# LoRa_ST_Sensor_Node_v1_0.net
KiCad netlist of a schematic drawn in EAGLE
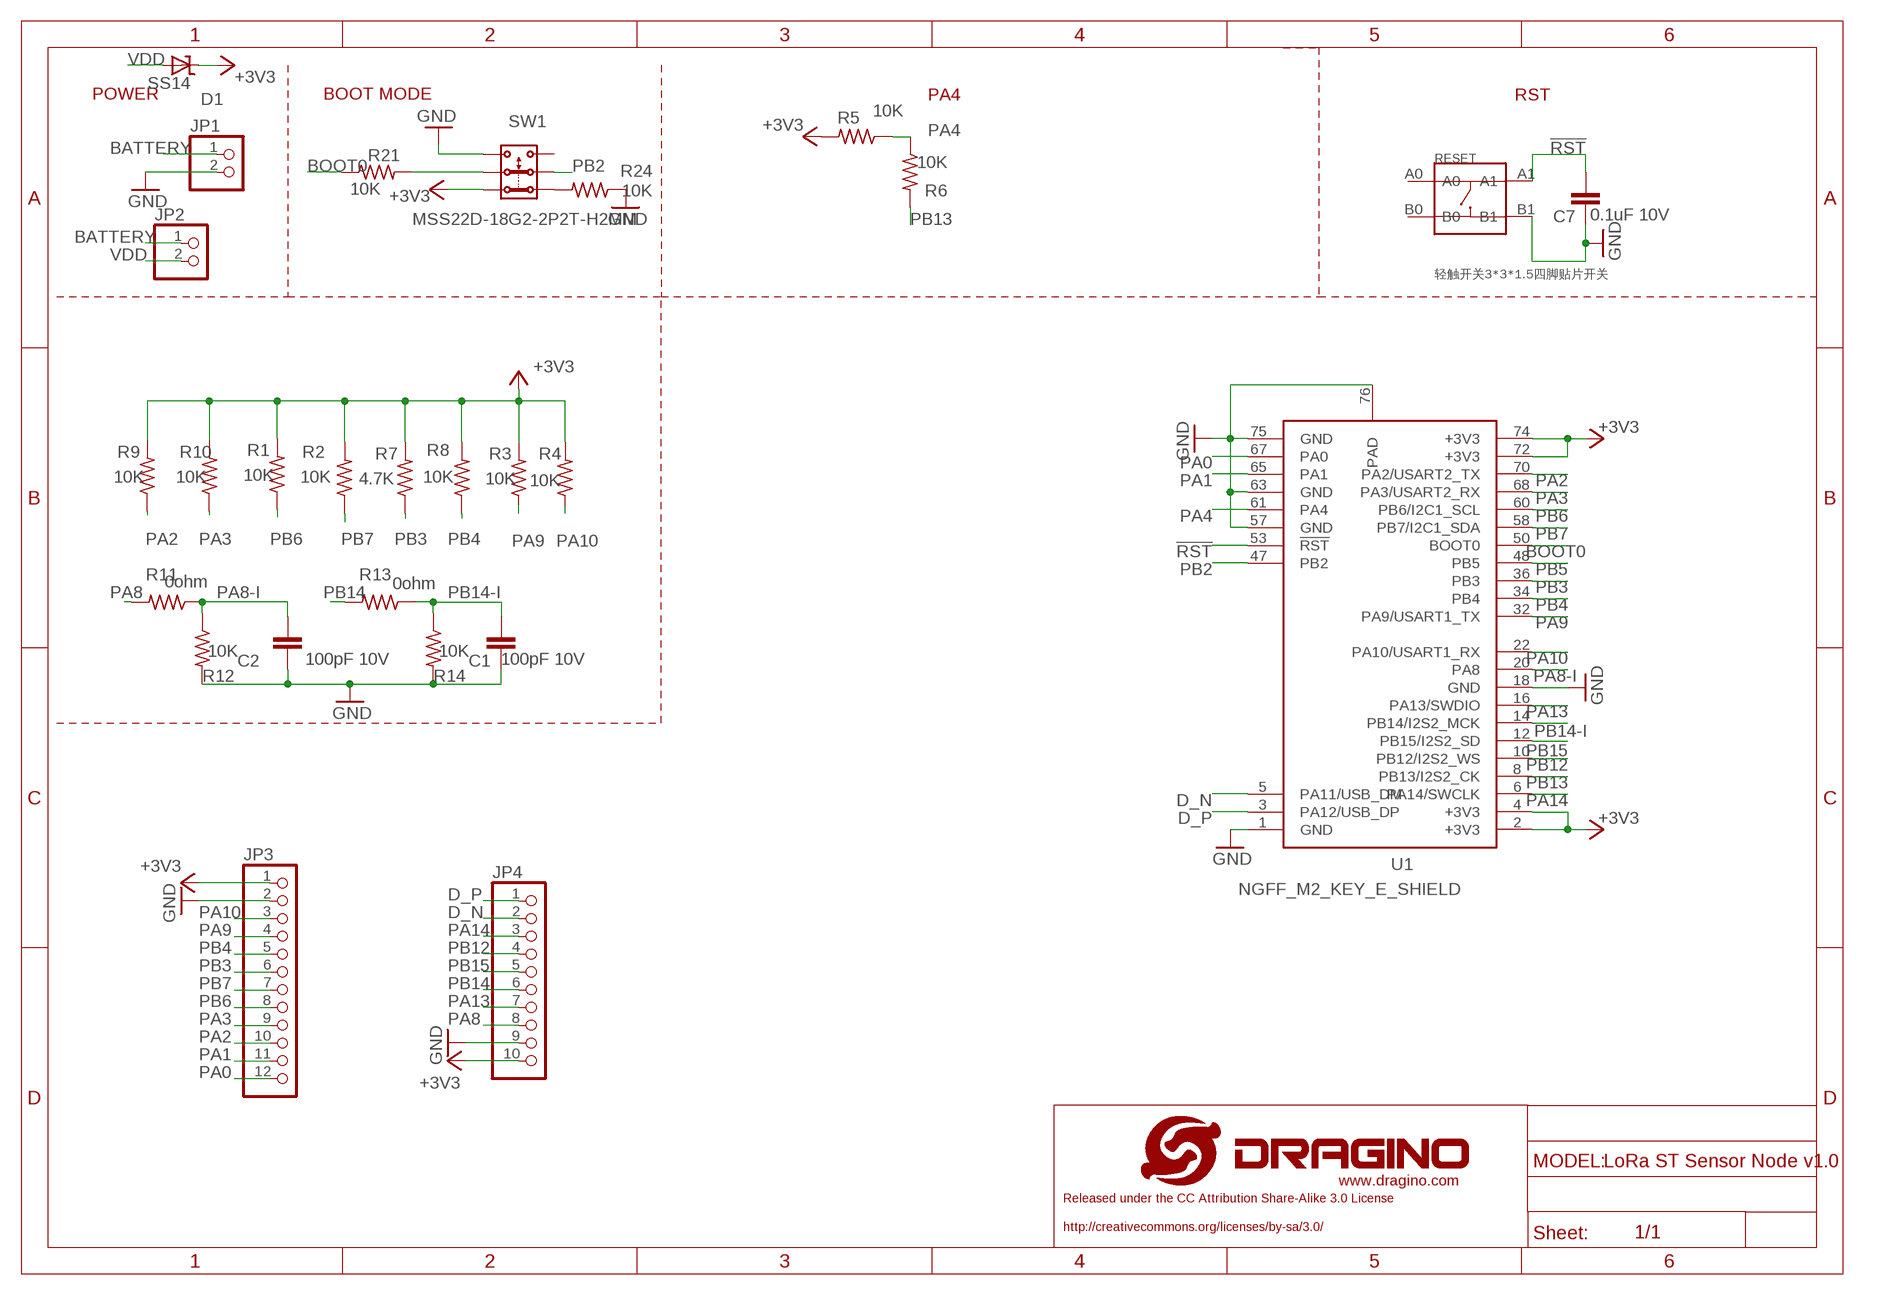
[diagram p0: schematic, sheet 1]

(export (version "E")
  (design (tool "Eeschema 10.0.6"))
  (components
    (comp (ref "C1")
      (value "100pF 10V")
      (footprint "eagle-import:C0603")
      (libsource (lib "eagle-import") (part "C-EUC0603"))
    )
    (comp (ref "C2")
      (value "100pF 10V")
      (footprint "eagle-import:C0603")
      (libsource (lib "eagle-import") (part "C-EUC0603"))
    )
    (comp (ref "C7")
      (value "0.1uF 10V")
      (footprint "eagle-import:C0402")
      (libsource (lib "eagle-import") (part "C-EUC0402"))
    )
    (comp (ref "D1")
      (value "SS14")
      (footprint "eagle-import:DO214AC")
      (libsource (lib "eagle-import") (part "SCHOTTKYSMBG"))
    )
    (comp (ref "JP1")
      (value "PINHD-1X2POWER")
      (footprint "eagle-import:1X02-SMD")
      (libsource (lib "eagle-import") (part "PINHD-1X2POWER"))
    )
    (comp (ref "JP2")
      (value "PINHD-1X2")
      (footprint "eagle-import:1X02")
      (libsource (lib "eagle-import") (part "PINHD-1X2"))
    )
    (comp (ref "JP3")
      (value "PINHD-1X12\"\"")
      (footprint "eagle-import:1X12-DIP")
      (libsource (lib "eagle-import") (part "PINHD-1X12{dblquote}{dblquote}"))
    )
    (comp (ref "JP4")
      (value "PINHD-1X10\"\"")
      (footprint "eagle-import:1X10-DIP")
      (libsource (lib "eagle-import") (part "PINHD-1X10{dblquote}{dblquote}"))
    )
    (comp (ref "R1")
      (value "10K")
      (footprint "eagle-import:R0402")
      (libsource (lib "eagle-import") (part "R-US_R0402"))
    )
    (comp (ref "R2")
      (value "10K")
      (footprint "eagle-import:R0402")
      (libsource (lib "eagle-import") (part "R-US_R0402"))
    )
    (comp (ref "R3")
      (value "10K")
      (footprint "eagle-import:R0402")
      (libsource (lib "eagle-import") (part "R-US_R0402"))
    )
    (comp (ref "R4")
      (value "10K")
      (footprint "eagle-import:R0402")
      (libsource (lib "eagle-import") (part "R-US_R0402"))
    )
    (comp (ref "R5")
      (value "10K")
      (footprint "eagle-import:R0402")
      (libsource (lib "eagle-import") (part "R-US_R0402"))
    )
    (comp (ref "R6")
      (value "10K")
      (footprint "eagle-import:R0402")
      (libsource (lib "eagle-import") (part "R-US_R0402"))
    )
    (comp (ref "R7")
      (value "4.7K")
      (footprint "eagle-import:R0402")
      (libsource (lib "eagle-import") (part "R-US_R0402"))
    )
    (comp (ref "R8")
      (value "10K")
      (footprint "eagle-import:R0402")
      (libsource (lib "eagle-import") (part "R-US_R0402"))
    )
    (comp (ref "R9")
      (value "10K")
      (footprint "eagle-import:R0402")
      (libsource (lib "eagle-import") (part "R-US_R0402"))
    )
    (comp (ref "R10")
      (value "10K")
      (footprint "eagle-import:R0402")
      (libsource (lib "eagle-import") (part "R-US_R0402"))
    )
    (comp (ref "R11")
      (value "0ohm")
      (footprint "eagle-import:R0603")
      (libsource (lib "eagle-import") (part "R-US_R0603"))
    )
    (comp (ref "R12")
      (value "10K")
      (footprint "eagle-import:R0603")
      (libsource (lib "eagle-import") (part "R-US_R0603"))
    )
    (comp (ref "R13")
      (value "0ohm")
      (footprint "eagle-import:R0603")
      (libsource (lib "eagle-import") (part "R-US_R0603"))
    )
    (comp (ref "R14")
      (value "10K")
      (footprint "eagle-import:R0603")
      (libsource (lib "eagle-import") (part "R-US_R0603"))
    )
    (comp (ref "R21")
      (value "10K")
      (footprint "eagle-import:R0402")
      (libsource (lib "eagle-import") (part "R-US_R0402"))
    )
    (comp (ref "R24")
      (value "10K")
      (footprint "eagle-import:R0402")
      (libsource (lib "eagle-import") (part "R-US_R0402"))
    )
    (comp (ref "RESET")
      (value "轻触开关3*3*1.5四脚贴片开关")
      (footprint "eagle-import:SW4-SMD-3.35X3.35X1.5MM")
      (libsource (lib "eagle-import") (part "BUTTON-4P-3.3X3.3"))
    )
    (comp (ref "SW1")
      (value "MSS22D-18G2-2P2T-H2MM")
      (footprint "eagle-import:MSS22D-18G2-2P2T-H2MM-DIL")
      (libsource (lib "eagle-import") (part "MSS22D-18G2-2P2T-H2MM"))
    )
    (comp (ref "U1")
      (value "NGFF_M2_KEY_E_SHIELD")
      (footprint "eagle-import:NGFF_M2_KEY_E_SHIELD")
      (libsource (lib "eagle-import") (part "NGFF_M2_KEY_E_SHIELD"))
    )
  )
  (nets
    (net (code "1") (name "+3V3") (class "Default")
      (node (ref "D1") (pin "C") (pinfunction "C_C") (pintype "passive"))
      (node (ref "JP3") (pin "1") (pinfunction "1_1") (pintype "passive"))
      (node (ref "JP4") (pin "10") (pinfunction "10_10") (pintype "passive"))
      (node (ref "R1") (pin "2") (pinfunction "2_2") (pintype "passive"))
      (node (ref "R10") (pin "2") (pinfunction "2_2") (pintype "passive"))
      (node (ref "R2") (pin "2") (pinfunction "2_2") (pintype "passive"))
      (node (ref "R3") (pin "2") (pinfunction "2_2") (pintype "passive"))
      (node (ref "R4") (pin "2") (pinfunction "2_2") (pintype "passive"))
      (node (ref "R5") (pin "2") (pinfunction "2_2") (pintype "passive"))
      (node (ref "R7") (pin "2") (pinfunction "2_2") (pintype "passive"))
      (node (ref "R8") (pin "2") (pinfunction "2_2") (pintype "passive"))
      (node (ref "R9") (pin "2") (pinfunction "2_2") (pintype "passive"))
      (node (ref "SW1") (pin "3") (pinfunction "3_3") (pintype "bidirectional"))
      (node (ref "U1") (pin "2") (pinfunction "+3V3_2") (pintype "bidirectional"))
      (node (ref "U1") (pin "4") (pinfunction "+3V3_4") (pintype "bidirectional"))
      (node (ref "U1") (pin "72") (pinfunction "+3V3_72") (pintype "bidirectional"))
      (node (ref "U1") (pin "74") (pinfunction "+3V3_74") (pintype "bidirectional"))
    )
    (net (code "2") (name "/BATTERY") (class "Default")
      (node (ref "JP1") (pin "1") (pinfunction "1_1") (pintype "passive"))
      (node (ref "JP2") (pin "1") (pinfunction "1_1") (pintype "passive"))
    )
    (net (code "3") (name "/BOOT0") (class "Default")
      (node (ref "R21") (pin "1") (pinfunction "1_1") (pintype "passive"))
      (node (ref "U1") (pin "50") (pinfunction "BOOT0_50") (pintype "bidirectional"))
    )
    (net (code "4") (name "/D_N") (class "Default")
      (node (ref "JP4") (pin "2") (pinfunction "2_2") (pintype "passive"))
      (node (ref "U1") (pin "5") (pinfunction "PA11/USB_DM_5") (pintype "bidirectional"))
    )
    (net (code "5") (name "/D_P") (class "Default")
      (node (ref "JP4") (pin "1") (pinfunction "1_1") (pintype "passive"))
      (node (ref "U1") (pin "3") (pinfunction "PA12/USB_DP_3") (pintype "bidirectional"))
    )
    (net (code "6") (name "/PA0") (class "Default")
      (node (ref "JP3") (pin "12") (pinfunction "12_12") (pintype "passive"))
      (node (ref "U1") (pin "67") (pinfunction "PA0_67") (pintype "bidirectional"))
    )
    (net (code "7") (name "/PA1") (class "Default")
      (node (ref "JP3") (pin "11") (pinfunction "11_11") (pintype "passive"))
      (node (ref "U1") (pin "65") (pinfunction "PA1_65") (pintype "bidirectional"))
    )
    (net (code "8") (name "/PA2") (class "Default")
      (node (ref "JP3") (pin "10") (pinfunction "10_10") (pintype "passive"))
      (node (ref "R9") (pin "1") (pinfunction "1_1") (pintype "passive"))
      (node (ref "U1") (pin "70") (pinfunction "PA2/USART2_TX_70") (pintype "bidirectional"))
    )
    (net (code "9") (name "/PA3") (class "Default")
      (node (ref "JP3") (pin "9") (pinfunction "9_9") (pintype "passive"))
      (node (ref "R10") (pin "1") (pinfunction "1_1") (pintype "passive"))
      (node (ref "U1") (pin "68") (pinfunction "PA3/USART2_RX_68") (pintype "bidirectional"))
    )
    (net (code "10") (name "/PA4") (class "Default")
      (node (ref "R5") (pin "1") (pinfunction "1_1") (pintype "passive"))
      (node (ref "R6") (pin "1") (pinfunction "1_1") (pintype "passive"))
      (node (ref "U1") (pin "61") (pinfunction "PA4_61") (pintype "bidirectional"))
    )
    (net (code "11") (name "/PA8") (class "Default")
      (node (ref "JP4") (pin "8") (pinfunction "8_8") (pintype "passive"))
      (node (ref "R11") (pin "2") (pinfunction "2_2") (pintype "passive"))
    )
    (net (code "12") (name "/PA8-I") (class "Default")
      (node (ref "C2") (pin "2") (pinfunction "2_2") (pintype "passive"))
      (node (ref "R11") (pin "1") (pinfunction "1_1") (pintype "passive"))
      (node (ref "R12") (pin "1") (pinfunction "1_1") (pintype "passive"))
      (node (ref "U1") (pin "20") (pinfunction "PA8_20") (pintype "bidirectional"))
    )
    (net (code "13") (name "/PA9") (class "Default")
      (node (ref "JP3") (pin "4") (pinfunction "4_4") (pintype "passive"))
      (node (ref "R3") (pin "1") (pinfunction "1_1") (pintype "passive"))
      (node (ref "U1") (pin "32") (pinfunction "PA9/USART1_TX_32") (pintype "bidirectional"))
    )
    (net (code "14") (name "/PA10") (class "Default")
      (node (ref "JP3") (pin "3") (pinfunction "3_3") (pintype "passive"))
      (node (ref "R4") (pin "1") (pinfunction "1_1") (pintype "passive"))
      (node (ref "U1") (pin "22") (pinfunction "PA10/USART1_RX_22") (pintype "bidirectional"))
    )
    (net (code "15") (name "/PA13") (class "Default")
      (node (ref "JP4") (pin "7") (pinfunction "7_7") (pintype "passive"))
      (node (ref "U1") (pin "16") (pinfunction "PA13/SWDIO_16") (pintype "bidirectional"))
    )
    (net (code "16") (name "/PA14") (class "Default")
      (node (ref "JP4") (pin "3") (pinfunction "3_3") (pintype "passive"))
      (node (ref "U1") (pin "6") (pinfunction "PA14/SWCLK_6") (pintype "bidirectional"))
    )
    (net (code "17") (name "/PB2") (class "Default")
      (node (ref "SW1") (pin "5") (pinfunction "5_5") (pintype "bidirectional"))
      (node (ref "U1") (pin "47") (pinfunction "PB2_47") (pintype "bidirectional"))
    )
    (net (code "18") (name "/PB3") (class "Default")
      (node (ref "JP3") (pin "6") (pinfunction "6_6") (pintype "passive"))
      (node (ref "R7") (pin "1") (pinfunction "1_1") (pintype "passive"))
      (node (ref "U1") (pin "36") (pinfunction "PB3_36") (pintype "bidirectional"))
    )
    (net (code "19") (name "/PB4") (class "Default")
      (node (ref "JP3") (pin "5") (pinfunction "5_5") (pintype "passive"))
      (node (ref "R8") (pin "1") (pinfunction "1_1") (pintype "passive"))
      (node (ref "U1") (pin "34") (pinfunction "PB4_34") (pintype "bidirectional"))
    )
    (net (code "20") (name "/PB5") (class "Default")
      (node (ref "U1") (pin "48") (pinfunction "PB5_48") (pintype "bidirectional"))
    )
    (net (code "21") (name "/PB6") (class "Default")
      (node (ref "JP3") (pin "8") (pinfunction "8_8") (pintype "passive"))
      (node (ref "R1") (pin "1") (pinfunction "1_1") (pintype "passive"))
      (node (ref "U1") (pin "60") (pinfunction "PB6/I2C1_SCL_60") (pintype "bidirectional"))
    )
    (net (code "22") (name "/PB7") (class "Default")
      (node (ref "JP3") (pin "7") (pinfunction "7_7") (pintype "passive"))
      (node (ref "R2") (pin "1") (pinfunction "1_1") (pintype "passive"))
      (node (ref "U1") (pin "58") (pinfunction "PB7/I2C1_SDA_58") (pintype "bidirectional"))
    )
    (net (code "23") (name "/PB12") (class "Default")
      (node (ref "JP4") (pin "4") (pinfunction "4_4") (pintype "passive"))
      (node (ref "U1") (pin "10") (pinfunction "PB12/I2S2_WS_10") (pintype "bidirectional"))
    )
    (net (code "24") (name "/PB13") (class "Default")
      (node (ref "R6") (pin "2") (pinfunction "2_2") (pintype "passive"))
      (node (ref "U1") (pin "8") (pinfunction "PB13/I2S2_CK_8") (pintype "bidirectional"))
    )
    (net (code "25") (name "/PB14") (class "Default")
      (node (ref "JP4") (pin "6") (pinfunction "6_6") (pintype "passive"))
      (node (ref "R13") (pin "2") (pinfunction "2_2") (pintype "passive"))
    )
    (net (code "26") (name "/PB14-I") (class "Default")
      (node (ref "C1") (pin "2") (pinfunction "2_2") (pintype "passive"))
      (node (ref "R13") (pin "1") (pinfunction "1_1") (pintype "passive"))
      (node (ref "R14") (pin "1") (pinfunction "1_1") (pintype "passive"))
      (node (ref "U1") (pin "14") (pinfunction "PB14/I2S2_MCK_14") (pintype "bidirectional"))
    )
    (net (code "27") (name "/PB15") (class "Default")
      (node (ref "JP4") (pin "5") (pinfunction "5_5") (pintype "passive"))
      (node (ref "U1") (pin "12") (pinfunction "PB15/I2S2_SD_12") (pintype "bidirectional"))
    )
    (net (code "28") (name "/VDD") (class "Default")
      (node (ref "D1") (pin "A") (pinfunction "A_A") (pintype "passive"))
      (node (ref "JP2") (pin "2") (pinfunction "2_2") (pintype "passive"))
    )
    (net (code "29") (name "/~{RST}") (class "Default")
      (node (ref "C7") (pin "2") (pinfunction "2_2") (pintype "passive"))
      (node (ref "RESET") (pin "A1") (pinfunction "A1_A1") (pintype "bidirectional"))
      (node (ref "U1") (pin "53") (pinfunction "~{RST}_53") (pintype "bidirectional"))
    )
    (net (code "30") (name "GND") (class "Default")
      (node (ref "C1") (pin "1") (pinfunction "1_1") (pintype "passive"))
      (node (ref "C2") (pin "1") (pinfunction "1_1") (pintype "passive"))
      (node (ref "C7") (pin "1") (pinfunction "1_1") (pintype "passive"))
      (node (ref "JP1") (pin "2") (pinfunction "2_2") (pintype "passive"))
      (node (ref "JP3") (pin "2") (pinfunction "2_2") (pintype "passive"))
      (node (ref "JP4") (pin "9") (pinfunction "9_9") (pintype "passive"))
      (node (ref "R12") (pin "2") (pinfunction "2_2") (pintype "passive"))
      (node (ref "R14") (pin "2") (pinfunction "2_2") (pintype "passive"))
      (node (ref "R24") (pin "1") (pinfunction "1_1") (pintype "passive"))
      (node (ref "RESET") (pin "B1") (pinfunction "B1_B1") (pintype "bidirectional"))
      (node (ref "SW1") (pin "1") (pinfunction "1_1") (pintype "bidirectional"))
      (node (ref "U1") (pin "1") (pinfunction "GND_1") (pintype "bidirectional"))
      (node (ref "U1") (pin "18") (pinfunction "GND_18") (pintype "bidirectional"))
      (node (ref "U1") (pin "57") (pinfunction "GND_57") (pintype "bidirectional"))
      (node (ref "U1") (pin "63") (pinfunction "GND_63") (pintype "bidirectional"))
      (node (ref "U1") (pin "75") (pinfunction "GND_75") (pintype "bidirectional"))
      (node (ref "U1") (pin "76") (pinfunction "PAD_76") (pintype "bidirectional"))
    )
    (net (code "31") (name "Net-(R21-Pad2)") (class "Default")
      (node (ref "R21") (pin "2") (pinfunction "2_2") (pintype "passive"))
      (node (ref "SW1") (pin "2") (pinfunction "2_2") (pintype "bidirectional"))
    )
    (net (code "32") (name "Net-(R24-Pad2)") (class "Default")
      (node (ref "R24") (pin "2") (pinfunction "2_2") (pintype "passive"))
      (node (ref "SW1") (pin "4") (pinfunction "4_4") (pintype "bidirectional"))
    )
    (net (code "33") (name "unconnected-(RESET-PadA0)") (class "Default")
      (node (ref "RESET") (pin "A0") (pinfunction "A0_A0") (pintype "bidirectional"))
    )
    (net (code "34") (name "unconnected-(RESET-PadB0)") (class "Default")
      (node (ref "RESET") (pin "B0") (pinfunction "B0_B0") (pintype "bidirectional"))
    )
    (net (code "35") (name "unconnected-(SW1-Pad6)") (class "Default")
      (node (ref "SW1") (pin "6") (pinfunction "6_6") (pintype "bidirectional"))
    )
  )
)
